# sch.net
KiCad netlist of a schematic drawn in Altium Designer
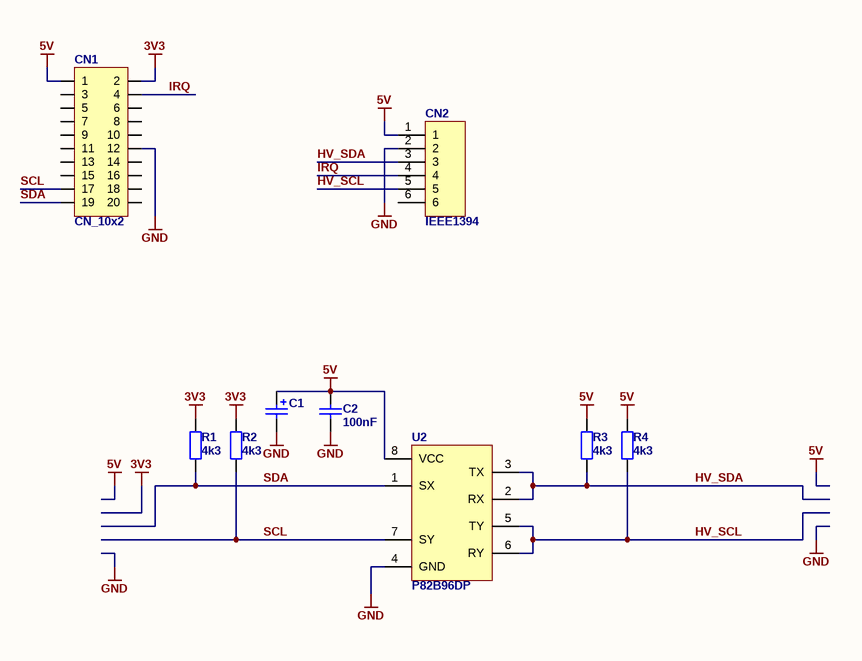
[diagram p0: sch.SchDoc]

(export (version "E")
  (design (tool "Eeschema 10.0.6"))
  (components
    (comp (ref "C1")
      (value "~")
      (footprint "SMDB")
      (description "Polarized Tantalum Capacitor")
      (libsource (lib "capacitors") (part "Cap Pol Tant"))
    )
    (comp (ref "C2")
      (value "100nF")
      (footprint "C0603")
      (description "Capacitor")
      (libsource (lib "capacitors") (part "Cap"))
    )
    (comp (ref "CN1")
      (value "CN_10x2")
      (footprint "GP_10x2")
      (libsource (lib "goldpin_male") (part "CN_10x2"))
    )
    (comp (ref "CN2")
      (value "IEEE1394")
      (footprint "A-IEE-DIP-C")
      (libsource (lib "connectors_other") (part "IEEE1394"))
    )
    (comp (ref "R1")
      (value "4k3")
      (footprint "R0805")
      (description "Resistor")
      (libsource (lib "resistors") (part "Res"))
    )
    (comp (ref "R2")
      (value "4k3")
      (footprint "R0805")
      (description "Resistor")
      (libsource (lib "resistors") (part "Res"))
    )
    (comp (ref "R3")
      (value "4k3")
      (footprint "R0603")
      (description "Resistor")
      (libsource (lib "resistors") (part "Res"))
    )
    (comp (ref "R4")
      (value "4k3")
      (footprint "R0603")
      (description "Resistor")
      (libsource (lib "resistors") (part "Res"))
    )
    (comp (ref "U2")
      (value "P82B96DP")
      (footprint "TSSOP8N")
      (description "Dual Bidirectional I2C Bus Buffer, TSSOP8 Package")
      (libsource (lib "i2c_other_ics") (part "P82B96DP"))
    )
  )
  (nets
    (net (code "1") (name "/HV_SCL") (class "Default")
      (node (ref "CN2") (pin "5") (pinfunction "5_5") (pintype "passive"))
      (node (ref "R4") (pin "1") (pinfunction "1_1") (pintype "passive"))
      (node (ref "U2") (pin "5") (pinfunction "TY_5") (pintype "passive"))
      (node (ref "U2") (pin "6") (pinfunction "RY_6") (pintype "passive"))
    )
    (net (code "2") (name "/HV_SDA") (class "Default")
      (node (ref "CN2") (pin "3") (pinfunction "3_3") (pintype "passive"))
      (node (ref "R3") (pin "1") (pinfunction "1_1") (pintype "passive"))
      (node (ref "U2") (pin "2") (pinfunction "RX_2") (pintype "passive"))
      (node (ref "U2") (pin "3") (pinfunction "TX_3") (pintype "passive"))
    )
    (net (code "3") (name "/IRQ") (class "Default")
      (node (ref "CN1") (pin "4") (pinfunction "4_4") (pintype "passive"))
      (node (ref "CN2") (pin "4") (pinfunction "4_4") (pintype "passive"))
    )
    (net (code "4") (name "/SCL") (class "Default")
      (node (ref "CN1") (pin "17") (pinfunction "17_17") (pintype "passive"))
      (node (ref "R2") (pin "1") (pinfunction "1_1") (pintype "passive"))
      (node (ref "U2") (pin "7") (pinfunction "SY_7") (pintype "passive"))
    )
    (net (code "5") (name "/SDA") (class "Default")
      (node (ref "CN1") (pin "19") (pinfunction "19_19") (pintype "passive"))
      (node (ref "R1") (pin "1") (pinfunction "1_1") (pintype "passive"))
      (node (ref "U2") (pin "1") (pinfunction "SX_1") (pintype "passive"))
    )
    (net (code "6") (name "3V3") (class "Default")
      (node (ref "CN1") (pin "2") (pinfunction "2_2") (pintype "passive"))
      (node (ref "R1") (pin "2") (pinfunction "2_2") (pintype "passive"))
      (node (ref "R2") (pin "2") (pinfunction "2_2") (pintype "passive"))
    )
    (net (code "7") (name "5V") (class "Default")
      (node (ref "C1") (pin "1") (pinfunction "1_1") (pintype "passive"))
      (node (ref "C2") (pin "2") (pinfunction "2_2") (pintype "passive"))
      (node (ref "CN1") (pin "1") (pinfunction "1_1") (pintype "passive"))
      (node (ref "CN2") (pin "1") (pinfunction "1_1") (pintype "passive"))
      (node (ref "R3") (pin "2") (pinfunction "2_2") (pintype "passive"))
      (node (ref "R4") (pin "2") (pinfunction "2_2") (pintype "passive"))
      (node (ref "U2") (pin "8") (pinfunction "VCC_8") (pintype "passive"))
    )
    (net (code "8") (name "GND") (class "Default")
      (node (ref "C1") (pin "2") (pinfunction "2_2") (pintype "passive"))
      (node (ref "C2") (pin "1") (pinfunction "1_1") (pintype "passive"))
      (node (ref "CN1") (pin "12") (pinfunction "12_12") (pintype "passive"))
      (node (ref "CN2") (pin "2") (pinfunction "2_2") (pintype "passive"))
      (node (ref "U2") (pin "4") (pinfunction "GND_4") (pintype "passive"))
    )
    (net (code "9") (name "unconnected-(CN1-Pad3)") (class "Default")
      (node (ref "CN1") (pin "3") (pinfunction "3_3") (pintype "passive"))
    )
    (net (code "10") (name "unconnected-(CN1-Pad5)") (class "Default")
      (node (ref "CN1") (pin "5") (pinfunction "5_5") (pintype "passive"))
    )
    (net (code "11") (name "unconnected-(CN1-Pad6)") (class "Default")
      (node (ref "CN1") (pin "6") (pinfunction "6_6") (pintype "passive"))
    )
    (net (code "12") (name "unconnected-(CN1-Pad7)") (class "Default")
      (node (ref "CN1") (pin "7") (pinfunction "7_7") (pintype "passive"))
    )
    (net (code "13") (name "unconnected-(CN1-Pad8)") (class "Default")
      (node (ref "CN1") (pin "8") (pinfunction "8_8") (pintype "passive"))
    )
    (net (code "14") (name "unconnected-(CN1-Pad9)") (class "Default")
      (node (ref "CN1") (pin "9") (pinfunction "9_9") (pintype "passive"))
    )
    (net (code "15") (name "unconnected-(CN1-Pad10)") (class "Default")
      (node (ref "CN1") (pin "10") (pinfunction "10_10") (pintype "passive"))
    )
    (net (code "16") (name "unconnected-(CN1-Pad11)") (class "Default")
      (node (ref "CN1") (pin "11") (pinfunction "11_11") (pintype "passive"))
    )
    (net (code "17") (name "unconnected-(CN1-Pad13)") (class "Default")
      (node (ref "CN1") (pin "13") (pinfunction "13_13") (pintype "passive"))
    )
    (net (code "18") (name "unconnected-(CN1-Pad14)") (class "Default")
      (node (ref "CN1") (pin "14") (pinfunction "14_14") (pintype "passive"))
    )
    (net (code "19") (name "unconnected-(CN1-Pad15)") (class "Default")
      (node (ref "CN1") (pin "15") (pinfunction "15_15") (pintype "passive"))
    )
    (net (code "20") (name "unconnected-(CN1-Pad16)") (class "Default")
      (node (ref "CN1") (pin "16") (pinfunction "16_16") (pintype "passive"))
    )
    (net (code "21") (name "unconnected-(CN1-Pad18)") (class "Default")
      (node (ref "CN1") (pin "18") (pinfunction "18_18") (pintype "passive"))
    )
    (net (code "22") (name "unconnected-(CN1-Pad20)") (class "Default")
      (node (ref "CN1") (pin "20") (pinfunction "20_20") (pintype "passive"))
    )
    (net (code "23") (name "unconnected-(CN2-Pad6)") (class "Default")
      (node (ref "CN2") (pin "6") (pinfunction "6_6") (pintype "passive"))
    )
  )
)
